# SL1_Xilinx_Spartan-IIE_PQ208_Rev1_01.net
KiCad netlist of a schematic drawn in Altium Designer
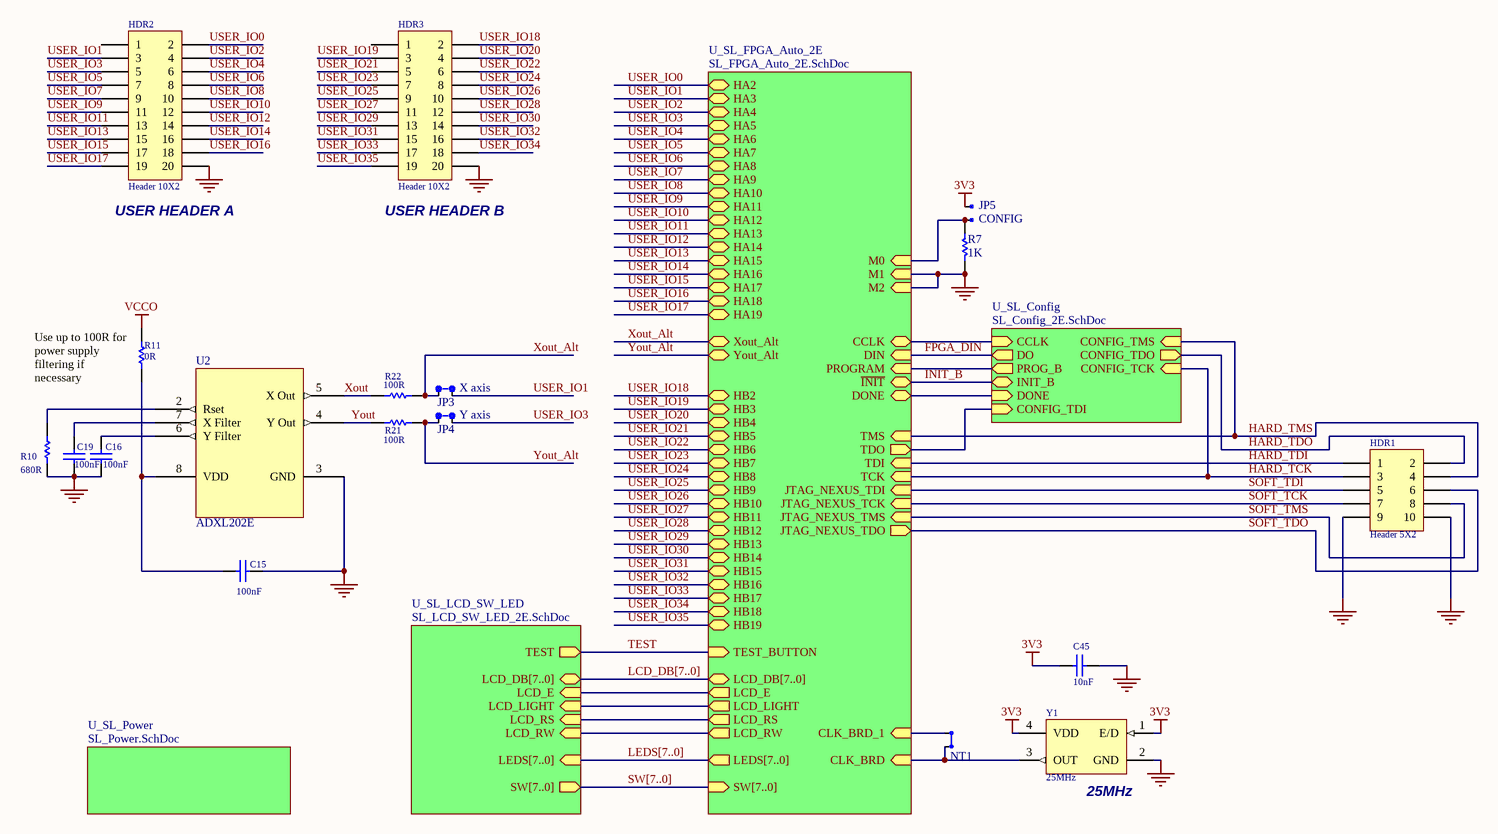
[diagram p0: SL1 Xilinx Spartan-IIE PQ208 Rev1.01.SchDoc]

(export (version "E")
  (design (tool "Eeschema 10.0.6"))
  (components
    (comp (ref "C15")
      (value "100nF")
      (footprint "CC1608-0603")
      (description "Capacitor")
      (libsource (lib "SpiritLevel_2E") (part "CAP"))
    )
    (comp (ref "C16")
      (value "100nF")
      (footprint "CC1608-0603")
      (description "Capacitor")
      (libsource (lib "SpiritLevel_2E") (part "CAP"))
    )
    (comp (ref "C19")
      (value "100nF")
      (footprint "CC1608-0603")
      (description "Capacitor")
      (libsource (lib "SpiritLevel_2E") (part "CAP"))
    )
    (comp (ref "C45")
      (value "10nF")
      (footprint "CC1608-0603")
      (description "Capacitor")
      (libsource (lib "SpiritLevel_2E") (part "CAP"))
    )
    (comp (ref "HDR1")
      (value "Header 5X2")
      (footprint "Spirit_Level_Project:HDR2X5_LP")
      (description "Header, 5-Pin, Dual row")
      (libsource (lib "SpiritLevel_2E") (part "Header 5X2"))
    )
    (comp (ref "HDR2")
      (value "Header 10X2")
      (footprint "Spirit_Level_Project:HDR2X10")
      (description "Header, 10-Pin, Dual row")
      (libsource (lib "SpiritLevel_2E") (part "Header 10X2"))
    )
    (comp (ref "HDR3")
      (value "Header 10X2")
      (footprint "Spirit_Level_Project:HDR2X10")
      (description "Header, 10-Pin, Dual row")
      (libsource (lib "SpiritLevel_2E") (part "Header 10X2"))
    )
    (comp (ref "JP3")
      (value "X axis")
      (footprint "Spirit_Level_Project:HDR1X2")
      (description "Jumper, 2-Pin")
      (libsource (lib "SpiritLevel_2E") (part "Jumper, 2-Pin"))
    )
    (comp (ref "JP4")
      (value "Y axis")
      (footprint "Spirit_Level_Project:HDR1X2")
      (description "Jumper, 2-Pin")
      (libsource (lib "SpiritLevel_2E") (part "Jumper, 2-Pin"))
    )
    (comp (ref "JP5")
      (value "CONFIG")
      (footprint "Spirit_Level_Project:HDR1X2")
      (description "Jumper, 2-Pin")
      (libsource (lib "SpiritLevel_2E") (part "Jumper, 2-Pin"))
    )
    (comp (ref "JS2")
      (value "Short Linking")
      (description "Shorting Link, 2.54mm (0.1\") Pitch")
      (libsource (lib "SpiritLevel_2E") (part "Jumper Socket"))
    )
    (comp (ref "JS3")
      (value "Shorting Link")
      (description "Shorting Link, 2.54mm (0.1\") Pitch")
      (libsource (lib "SpiritLevel_2E") (part "Jumper Socket"))
    )
    (comp (ref "NT1")
      (value "GND")
      (footprint "Spirit_Level_Project:NT")
      (description "Jumper, 2-Pin")
      (libsource (lib "SpiritLevel_2E") (part "Jumper, 2-Pin_1"))
    )
    (comp (ref "R7")
      (value "1K")
      (footprint "Spirit_Level_Project:CR2012-0805")
      (description "Resistor")
      (libsource (lib "SpiritLevel_2E") (part "RES"))
    )
    (comp (ref "R10")
      (value "680R")
      (footprint "Spirit_Level_Project:CR2012-0805")
      (description "Resistor")
      (libsource (lib "SpiritLevel_2E") (part "Res1"))
    )
    (comp (ref "R11")
      (value "0R")
      (footprint "Spirit_Level_Project:CR2012-0805")
      (description "Resistor")
      (libsource (lib "SpiritLevel_2E") (part "RES"))
    )
    (comp (ref "R21")
      (value "100R")
      (footprint "Spirit_Level_Project:CR2012-0805")
      (description "Resistor")
      (libsource (lib "SpiritLevel_2E") (part "Res1"))
    )
    (comp (ref "R22")
      (value "100R")
      (footprint "Spirit_Level_Project:CR2012-0805")
      (description "Resistor")
      (libsource (lib "SpiritLevel_2E") (part "Res1"))
    )
    (comp (ref "U2")
      (value "ADXL202E")
      (footprint "Spirit_Level_Project:E-8")
      (description "Accelerometer with Digital Output")
      (libsource (lib "SpiritLevel_2E") (part "ADXL202E"))
    )
    (comp (ref "Y1")
      (value "25MHz")
      (footprint "Spirit_Level_Project:QSMO_4200")
      (description "Surface Mount Crystal Oscillator")
      (libsource (lib "SpiritLevel_2E") (part "QSMO_4200"))
    )
  )
  (nets
    (net (code "26") (name "/CLK_BRD") (class "Default")
      (node (ref "NT1") (pin "2") (pinfunction "2_2") (pintype "passive"))
      (node (ref "Y1") (pin "3") (pinfunction "OUT_3") (pintype "output"))
    )
    (net (code "27") (name "/CLK_BRD_1") (class "Default")
      (node (ref "NT1") (pin "1") (pinfunction "1_1") (pintype "passive"))
    )
    (net (code "30") (name "/HARD_TCK") (class "Default")
      (node (ref "HDR1") (pin "3") (pinfunction "3_3") (pintype "passive"))
    )
    (net (code "31") (name "/HARD_TDI") (class "Default")
      (node (ref "HDR1") (pin "1") (pinfunction "1_1") (pintype "passive"))
    )
    (net (code "32") (name "/HARD_TDO") (class "Default")
      (node (ref "HDR1") (pin "2") (pinfunction "2_2") (pintype "passive"))
    )
    (net (code "33") (name "/HARD_TMS") (class "Default")
      (node (ref "HDR1") (pin "4") (pinfunction "4_4") (pintype "passive"))
    )
    (net (code "41") (name "/M0") (class "Default")
      (node (ref "JP5") (pin "1") (pinfunction "1_1") (pintype "passive"))
      (node (ref "R7") (pin "2") (pinfunction "2_2") (pintype "passive"))
    )
    (net (code "43") (name "/SOFT_TCK") (class "Default")
      (node (ref "HDR1") (pin "7") (pinfunction "7_7") (pintype "passive"))
    )
    (net (code "44") (name "/SOFT_TDI") (class "Default")
      (node (ref "HDR1") (pin "5") (pinfunction "5_5") (pintype "passive"))
    )
    (net (code "45") (name "/SOFT_TDO") (class "Default")
      (node (ref "HDR1") (pin "6") (pinfunction "6_6") (pintype "passive"))
    )
    (net (code "46") (name "/SOFT_TMS") (class "Default")
      (node (ref "HDR1") (pin "8") (pinfunction "8_8") (pintype "passive"))
    )
    (net (code "50") (name "/USER_IO0") (class "Default")
      (node (ref "HDR2") (pin "2") (pinfunction "2_2") (pintype "passive"))
    )
    (net (code "51") (name "/USER_IO1") (class "Default")
      (node (ref "HDR2") (pin "3") (pinfunction "3_3") (pintype "passive"))
      (node (ref "JP3") (pin "2") (pinfunction "2_2") (pintype "passive"))
    )
    (net (code "52") (name "/USER_IO2") (class "Default")
      (node (ref "HDR2") (pin "4") (pinfunction "4_4") (pintype "passive"))
    )
    (net (code "53") (name "/USER_IO3") (class "Default")
      (node (ref "HDR2") (pin "5") (pinfunction "5_5") (pintype "passive"))
      (node (ref "JP4") (pin "2") (pinfunction "2_2") (pintype "passive"))
    )
    (net (code "54") (name "/USER_IO4") (class "Default")
      (node (ref "HDR2") (pin "6") (pinfunction "6_6") (pintype "passive"))
    )
    (net (code "55") (name "/USER_IO5") (class "Default")
      (node (ref "HDR2") (pin "7") (pinfunction "7_7") (pintype "passive"))
    )
    (net (code "56") (name "/USER_IO6") (class "Default")
      (node (ref "HDR2") (pin "8") (pinfunction "8_8") (pintype "passive"))
    )
    (net (code "57") (name "/USER_IO7") (class "Default")
      (node (ref "HDR2") (pin "9") (pinfunction "9_9") (pintype "passive"))
    )
    (net (code "58") (name "/USER_IO8") (class "Default")
      (node (ref "HDR2") (pin "10") (pinfunction "10_10") (pintype "passive"))
    )
    (net (code "59") (name "/USER_IO9") (class "Default")
      (node (ref "HDR2") (pin "11") (pinfunction "11_11") (pintype "passive"))
    )
    (net (code "60") (name "/USER_IO10") (class "Default")
      (node (ref "HDR2") (pin "12") (pinfunction "12_12") (pintype "passive"))
    )
    (net (code "61") (name "/USER_IO11") (class "Default")
      (node (ref "HDR2") (pin "13") (pinfunction "13_13") (pintype "passive"))
    )
    (net (code "62") (name "/USER_IO12") (class "Default")
      (node (ref "HDR2") (pin "14") (pinfunction "14_14") (pintype "passive"))
    )
    (net (code "63") (name "/USER_IO13") (class "Default")
      (node (ref "HDR2") (pin "15") (pinfunction "15_15") (pintype "passive"))
    )
    (net (code "64") (name "/USER_IO14") (class "Default")
      (node (ref "HDR2") (pin "16") (pinfunction "16_16") (pintype "passive"))
    )
    (net (code "65") (name "/USER_IO15") (class "Default")
      (node (ref "HDR2") (pin "17") (pinfunction "17_17") (pintype "passive"))
    )
    (net (code "66") (name "/USER_IO16") (class "Default")
      (node (ref "HDR2") (pin "18") (pinfunction "18_18") (pintype "passive"))
    )
    (net (code "67") (name "/USER_IO17") (class "Default")
      (node (ref "HDR2") (pin "19") (pinfunction "19_19") (pintype "passive"))
    )
    (net (code "68") (name "/USER_IO18") (class "Default")
      (node (ref "HDR3") (pin "2") (pinfunction "2_2") (pintype "passive"))
    )
    (net (code "69") (name "/USER_IO19") (class "Default")
      (node (ref "HDR3") (pin "3") (pinfunction "3_3") (pintype "passive"))
    )
    (net (code "70") (name "/USER_IO20") (class "Default")
      (node (ref "HDR3") (pin "4") (pinfunction "4_4") (pintype "passive"))
    )
    (net (code "71") (name "/USER_IO21") (class "Default")
      (node (ref "HDR3") (pin "5") (pinfunction "5_5") (pintype "passive"))
    )
    (net (code "72") (name "/USER_IO22") (class "Default")
      (node (ref "HDR3") (pin "6") (pinfunction "6_6") (pintype "passive"))
    )
    (net (code "73") (name "/USER_IO23") (class "Default")
      (node (ref "HDR3") (pin "7") (pinfunction "7_7") (pintype "passive"))
    )
    (net (code "74") (name "/USER_IO24") (class "Default")
      (node (ref "HDR3") (pin "8") (pinfunction "8_8") (pintype "passive"))
    )
    (net (code "75") (name "/USER_IO25") (class "Default")
      (node (ref "HDR3") (pin "9") (pinfunction "9_9") (pintype "passive"))
    )
    (net (code "76") (name "/USER_IO26") (class "Default")
      (node (ref "HDR3") (pin "10") (pinfunction "10_10") (pintype "passive"))
    )
    (net (code "77") (name "/USER_IO27") (class "Default")
      (node (ref "HDR3") (pin "11") (pinfunction "11_11") (pintype "passive"))
    )
    (net (code "78") (name "/USER_IO28") (class "Default")
      (node (ref "HDR3") (pin "12") (pinfunction "12_12") (pintype "passive"))
    )
    (net (code "79") (name "/USER_IO29") (class "Default")
      (node (ref "HDR3") (pin "13") (pinfunction "13_13") (pintype "passive"))
    )
    (net (code "80") (name "/USER_IO30") (class "Default")
      (node (ref "HDR3") (pin "14") (pinfunction "14_14") (pintype "passive"))
    )
    (net (code "81") (name "/USER_IO31") (class "Default")
      (node (ref "HDR3") (pin "15") (pinfunction "15_15") (pintype "passive"))
    )
    (net (code "82") (name "/USER_IO32") (class "Default")
      (node (ref "HDR3") (pin "16") (pinfunction "16_16") (pintype "passive"))
    )
    (net (code "83") (name "/USER_IO33") (class "Default")
      (node (ref "HDR3") (pin "17") (pinfunction "17_17") (pintype "passive"))
    )
    (net (code "84") (name "/USER_IO34") (class "Default")
      (node (ref "HDR3") (pin "18") (pinfunction "18_18") (pintype "passive"))
    )
    (net (code "85") (name "/USER_IO35") (class "Default")
      (node (ref "HDR3") (pin "19") (pinfunction "19_19") (pintype "passive"))
    )
    (net (code "86") (name "/Xout") (class "Default")
      (node (ref "R22") (pin "2") (pinfunction "2_2") (pintype "passive"))
      (node (ref "U2") (pin "5") (pinfunction "X_Out_5") (pintype "output"))
    )
    (net (code "87") (name "/Xout_Alt") (class "Default")
      (node (ref "JP3") (pin "1") (pinfunction "1_1") (pintype "passive"))
      (node (ref "R22") (pin "1") (pinfunction "1_1") (pintype "passive"))
    )
    (net (code "88") (name "/Yout") (class "Default")
      (node (ref "R21") (pin "2") (pinfunction "2_2") (pintype "passive"))
      (node (ref "U2") (pin "4") (pinfunction "Y_Out_4") (pintype "output"))
    )
    (net (code "89") (name "/Yout_Alt") (class "Default")
      (node (ref "JP4") (pin "1") (pinfunction "1_1") (pintype "passive"))
      (node (ref "R21") (pin "1") (pinfunction "1_1") (pintype "passive"))
    )
    (net (code "90") (name "3V3") (class "Default")
      (node (ref "C45") (pin "1") (pinfunction "1_1") (pintype "passive"))
      (node (ref "JP5") (pin "2") (pinfunction "2_2") (pintype "passive"))
      (node (ref "Y1") (pin "1") (pinfunction "E/D_1") (pintype "input"))
      (node (ref "Y1") (pin "4") (pinfunction "VDD_4") (pintype "power_in"))
    )
    (net (code "91") (name "GND") (class "Default")
      (node (ref "C15") (pin "2") (pinfunction "2_2") (pintype "passive"))
      (node (ref "C16") (pin "2") (pinfunction "2_2") (pintype "passive"))
      (node (ref "C19") (pin "2") (pinfunction "2_2") (pintype "passive"))
      (node (ref "C45") (pin "2") (pinfunction "2_2") (pintype "passive"))
      (node (ref "HDR1") (pin "10") (pinfunction "10_10") (pintype "passive"))
      (node (ref "HDR1") (pin "9") (pinfunction "9_9") (pintype "passive"))
      (node (ref "HDR2") (pin "20") (pinfunction "20_20") (pintype "passive"))
      (node (ref "HDR3") (pin "20") (pinfunction "20_20") (pintype "passive"))
      (node (ref "R10") (pin "1") (pinfunction "1_1") (pintype "passive"))
      (node (ref "R7") (pin "1") (pinfunction "1_1") (pintype "passive"))
      (node (ref "U2") (pin "3") (pinfunction "GND_3") (pintype "power_in"))
      (node (ref "Y1") (pin "2") (pinfunction "GND_2") (pintype "power_in"))
    )
    (net (code "92") (name "Net-(U2-Rset)") (class "Default")
      (node (ref "R10") (pin "2") (pinfunction "2_2") (pintype "passive"))
      (node (ref "U2") (pin "2") (pinfunction "Rset_2") (pintype "output"))
    )
    (net (code "93") (name "Net-(U2-VDD)") (class "Default")
      (node (ref "C15") (pin "1") (pinfunction "1_1") (pintype "passive"))
      (node (ref "R11") (pin "2") (pinfunction "2_2") (pintype "passive"))
      (node (ref "U2") (pin "8") (pinfunction "VDD_8") (pintype "power_in"))
    )
    (net (code "94") (name "Net-(U2-X_Filter)") (class "Default")
      (node (ref "C19") (pin "1") (pinfunction "1_1") (pintype "passive"))
      (node (ref "U2") (pin "7") (pinfunction "X_Filter_7") (pintype "output"))
    )
    (net (code "95") (name "Net-(U2-Y_Filter)") (class "Default")
      (node (ref "C16") (pin "1") (pinfunction "1_1") (pintype "passive"))
      (node (ref "U2") (pin "6") (pinfunction "Y_Filter_6") (pintype "output"))
    )
    (net (code "96") (name "VCCO") (class "Default")
      (node (ref "R11") (pin "1") (pinfunction "1_1") (pintype "passive"))
    )
    (net (code "97") (name "unconnected-(HDR2-Pad1)") (class "Default")
      (node (ref "HDR2") (pin "1") (pinfunction "1_1") (pintype "passive"))
    )
    (net (code "98") (name "unconnected-(HDR3-Pad1)") (class "Default")
      (node (ref "HDR3") (pin "1") (pinfunction "1_1") (pintype "passive"))
    )
    (net (code "99") (name "unconnected-(U2-Self_Test-Pad1)") (class "Default")
      (node (ref "U2") (pin "1") (pinfunction "Self_Test_1") (pintype "input"))
    )
  )
)
